# working.net
KiCad netlist of a schematic drawn in EAGLE
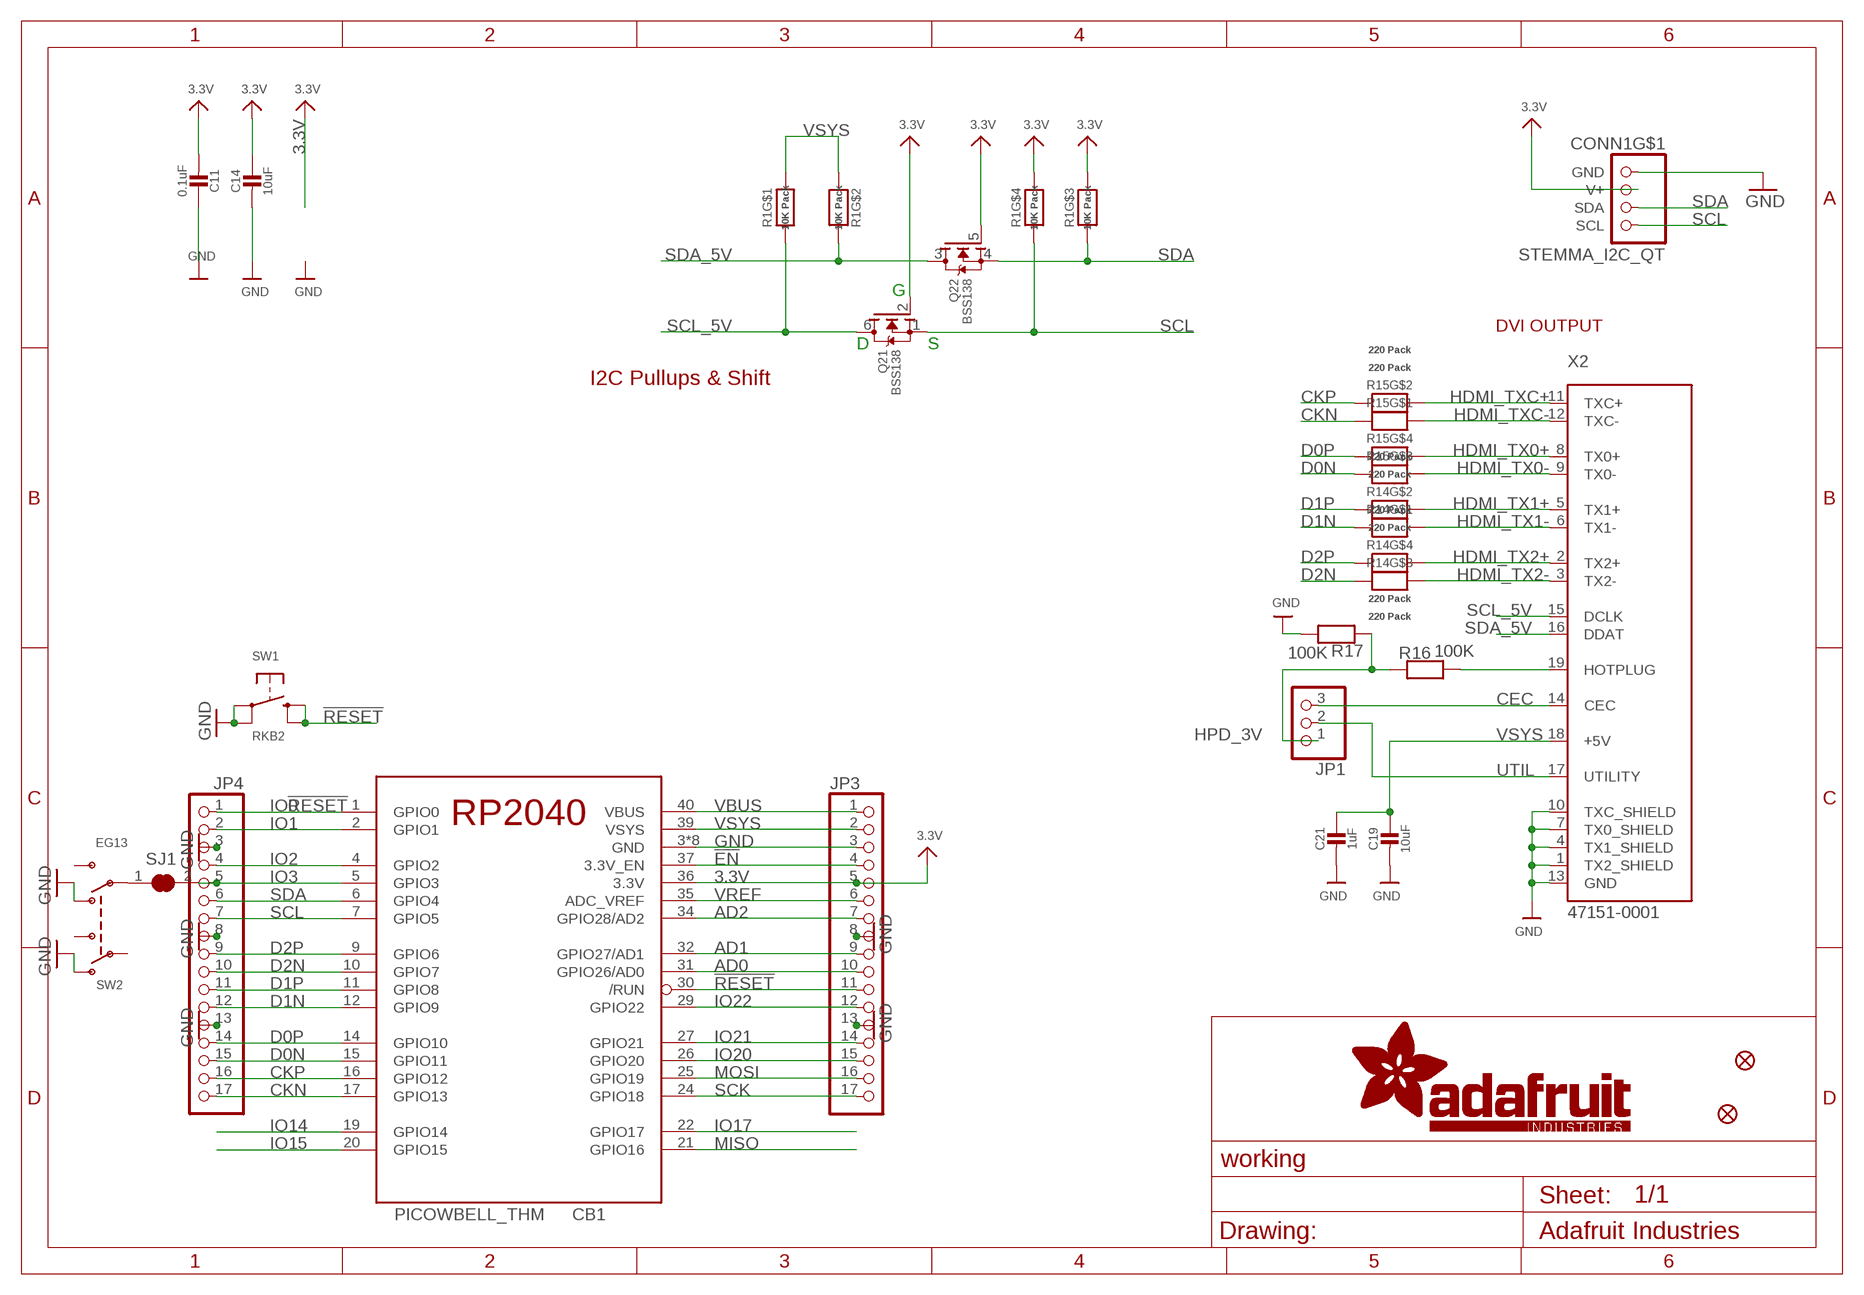
[diagram p0: schematic, sheet 1]

(export (version "E")
  (design (tool "Eeschema 10.0.6"))
  (components
    (comp (ref "C11")
      (value "0.1uF")
      (footprint "eagle-import:0603-NO")
      (libsource (lib "eagle-import") (part "CAP_CERAMIC0603_NO"))
    )
    (comp (ref "C14")
      (value "10uF")
      (footprint "eagle-import:0805-NO")
      (libsource (lib "eagle-import") (part "CAP_CERAMIC0805-NOOUTLINE"))
    )
    (comp (ref "C19")
      (value "10uF")
      (footprint "eagle-import:0805-NO")
      (fields (field (name "REV") "A"))
      (libsource (lib "eagle-import") (part "CAP_CERAMIC0805-NOOUTLINE"))
    )
    (comp (ref "C21")
      (value "1uF")
      (footprint "eagle-import:0603-NO")
      (libsource (lib "eagle-import") (part "CAP_CERAMIC0603_NO"))
    )
    (comp (ref "CB1")
      (value "PICOWBELL_THM")
      (footprint "eagle-import:PICOWBELL_THM")
      (libsource (lib "eagle-import") (part "PICOWBELL_THM"))
    )
    (comp (ref "CONN1")
      (value "STEMMA_I2C_QT")
      (footprint "eagle-import:JST_SH4")
      (libsource (lib "eagle-import") (part "STEMMA_I2C_QT"))
    )
    (comp (ref "FID1")
      (value "FIDUCIAL_1MM")
      (footprint "eagle-import:FIDUCIAL_1MM")
      (libsource (lib "eagle-import") (part "FIDUCIAL_1MM"))
    )
    (comp (ref "FID2")
      (value "FIDUCIAL_1MM")
      (footprint "eagle-import:FIDUCIAL_1MM")
      (libsource (lib "eagle-import") (part "FIDUCIAL_1MM"))
    )
    (comp (ref "JP1")
      (value "HEADER-1X3ROUND")
      (footprint "eagle-import:1X03_ROUND")
      (libsource (lib "eagle-import") (part "HEADER-1X3ROUND"))
    )
    (comp (ref "JP3")
      (value "HEADER-1X17")
      (footprint "eagle-import:1X17_ROUND70")
      (libsource (lib "eagle-import") (part "HEADER-1X17"))
    )
    (comp (ref "JP4")
      (value "HEADER-1X17")
      (footprint "eagle-import:1X17_ROUND70")
      (libsource (lib "eagle-import") (part "HEADER-1X17"))
    )
    (comp (ref "Q2")
      (value "BSS138")
      (footprint "eagle-import:SOT363")
      (libsource (lib "eagle-import") (part "MOSFET-N_DUAL"))
    )
    (comp (ref "R1")
      (value "10K Pack")
      (footprint "eagle-import:RESPACK_4X0603")
      (libsource (lib "eagle-import") (part "RESISTOR_4PACK"))
    )
    (comp (ref "R14")
      (value "220 Pack")
      (footprint "eagle-import:RESPACK_4X0603")
      (libsource (lib "eagle-import") (part "RESISTOR_4PACK"))
    )
    (comp (ref "R15")
      (value "220 Pack")
      (footprint "eagle-import:RESPACK_4X0603")
      (libsource (lib "eagle-import") (part "RESISTOR_4PACK"))
    )
    (comp (ref "R16")
      (value "100K")
      (footprint "eagle-import:0603-NO")
      (libsource (lib "eagle-import") (part "RESISTOR_0603_NOOUT"))
    )
    (comp (ref "R17")
      (value "100K")
      (footprint "eagle-import:0603-NO")
      (libsource (lib "eagle-import") (part "RESISTOR_0603_NOOUT"))
    )
    (comp (ref "SJ1")
      (value "SOLDERJUMPER_CLOSED")
      (footprint "eagle-import:SOLDERJUMPER_CLOSEDWIRE")
      (libsource (lib "eagle-import") (part "SOLDERJUMPER_CLOSED"))
    )
    (comp (ref "SW1")
      (value "RKB2")
      (footprint "eagle-import:BTN_RKB2_4.6X2.8")
      (libsource (lib "eagle-import") (part "SWITCH_TACT_SMT_RKB2"))
    )
    (comp (ref "SW2")
      (value "EG13")
      (footprint "eagle-import:EG1390")
      (libsource (lib "eagle-import") (part "SWITCH_DPDTEG1390"))
    )
    (comp (ref "X2")
      (value "47151-0001")
      (footprint "eagle-import:MINIHDMI_CNCTECH")
      (libsource (lib "eagle-import") (part "HDMI_MOLEX_47151_MINI"))
    )
  )
  (nets
    (net (code "1") (name "/AD0") (class "Default")
      (node (ref "CB1") (pin "31") (pinfunction "GPIO26/AD0_31") (pintype "bidirectional"))
      (node (ref "JP3") (pin "10") (pinfunction "10_10") (pintype "passive"))
    )
    (net (code "2") (name "/AD1") (class "Default")
      (node (ref "CB1") (pin "32") (pinfunction "GPIO27/AD1_32") (pintype "bidirectional"))
      (node (ref "JP3") (pin "9") (pinfunction "9_9") (pintype "passive"))
    )
    (net (code "3") (name "/AD2") (class "Default")
      (node (ref "CB1") (pin "34") (pinfunction "GPIO28/AD2_34") (pintype "bidirectional"))
      (node (ref "JP3") (pin "7") (pinfunction "7_7") (pintype "passive"))
    )
    (net (code "4") (name "/CEC") (class "Default")
      (node (ref "JP1") (pin "3") (pinfunction "3_3") (pintype "passive"))
      (node (ref "X2") (pin "14") (pinfunction "CEC_14") (pintype "bidirectional"))
    )
    (net (code "5") (name "/CKN") (class "Default")
      (node (ref "CB1") (pin "17") (pinfunction "GPIO13_17") (pintype "bidirectional"))
      (node (ref "JP4") (pin "17") (pinfunction "17_17") (pintype "passive"))
      (node (ref "R15") (pin "8") (pinfunction "2_8") (pintype "passive"))
    )
    (net (code "6") (name "/CKP") (class "Default")
      (node (ref "CB1") (pin "16") (pinfunction "GPIO12_16") (pintype "bidirectional"))
      (node (ref "JP4") (pin "16") (pinfunction "16_16") (pintype "passive"))
      (node (ref "R15") (pin "7") (pinfunction "2_7") (pintype "passive"))
    )
    (net (code "7") (name "/D0N") (class "Default")
      (node (ref "CB1") (pin "15") (pinfunction "GPIO11_15") (pintype "bidirectional"))
      (node (ref "JP4") (pin "15") (pinfunction "15_15") (pintype "passive"))
      (node (ref "R15") (pin "6") (pinfunction "2_6") (pintype "passive"))
    )
    (net (code "8") (name "/D0P") (class "Default")
      (node (ref "CB1") (pin "14") (pinfunction "GPIO10_14") (pintype "bidirectional"))
      (node (ref "JP4") (pin "14") (pinfunction "14_14") (pintype "passive"))
      (node (ref "R15") (pin "5") (pinfunction "2_5") (pintype "passive"))
    )
    (net (code "9") (name "/D1N") (class "Default")
      (node (ref "CB1") (pin "12") (pinfunction "GPIO9_12") (pintype "bidirectional"))
      (node (ref "JP4") (pin "12") (pinfunction "12_12") (pintype "passive"))
      (node (ref "R14") (pin "8") (pinfunction "2_8") (pintype "passive"))
    )
    (net (code "10") (name "/D1P") (class "Default")
      (node (ref "CB1") (pin "11") (pinfunction "GPIO8_11") (pintype "bidirectional"))
      (node (ref "JP4") (pin "11") (pinfunction "11_11") (pintype "passive"))
      (node (ref "R14") (pin "7") (pinfunction "2_7") (pintype "passive"))
    )
    (net (code "11") (name "/D2N") (class "Default")
      (node (ref "CB1") (pin "10") (pinfunction "GPIO7_10") (pintype "bidirectional"))
      (node (ref "JP4") (pin "10") (pinfunction "10_10") (pintype "passive"))
      (node (ref "R14") (pin "6") (pinfunction "2_6") (pintype "passive"))
    )
    (net (code "12") (name "/D2P") (class "Default")
      (node (ref "CB1") (pin "9") (pinfunction "GPIO6_9") (pintype "bidirectional"))
      (node (ref "JP4") (pin "9") (pinfunction "9_9") (pintype "passive"))
      (node (ref "R14") (pin "5") (pinfunction "2_5") (pintype "passive"))
    )
    (net (code "13") (name "/HDMI_TX0+") (class "Default")
      (node (ref "R15") (pin "4") (pinfunction "1_4") (pintype "passive"))
      (node (ref "X2") (pin "8") (pinfunction "TX0+_8") (pintype "bidirectional"))
    )
    (net (code "14") (name "/HDMI_TX0-") (class "Default")
      (node (ref "R15") (pin "3") (pinfunction "1_3") (pintype "passive"))
      (node (ref "X2") (pin "9") (pinfunction "TX0-_9") (pintype "bidirectional"))
    )
    (net (code "15") (name "/HDMI_TX1+") (class "Default")
      (node (ref "R14") (pin "2") (pinfunction "1_2") (pintype "passive"))
      (node (ref "X2") (pin "5") (pinfunction "TX1+_5") (pintype "bidirectional"))
    )
    (net (code "16") (name "/HDMI_TX1-") (class "Default")
      (node (ref "R14") (pin "1") (pinfunction "1_1") (pintype "passive"))
      (node (ref "X2") (pin "6") (pinfunction "TX1-_6") (pintype "bidirectional"))
    )
    (net (code "17") (name "/HDMI_TX2+") (class "Default")
      (node (ref "R14") (pin "4") (pinfunction "1_4") (pintype "passive"))
      (node (ref "X2") (pin "2") (pinfunction "TX2+_2") (pintype "bidirectional"))
    )
    (net (code "18") (name "/HDMI_TX2-") (class "Default")
      (node (ref "R14") (pin "3") (pinfunction "1_3") (pintype "passive"))
      (node (ref "X2") (pin "3") (pinfunction "TX2-_3") (pintype "bidirectional"))
    )
    (net (code "19") (name "/HDMI_TXC+") (class "Default")
      (node (ref "R15") (pin "2") (pinfunction "1_2") (pintype "passive"))
      (node (ref "X2") (pin "11") (pinfunction "TXC+_11") (pintype "bidirectional"))
    )
    (net (code "20") (name "/HDMI_TXC-") (class "Default")
      (node (ref "R15") (pin "1") (pinfunction "1_1") (pintype "passive"))
      (node (ref "X2") (pin "12") (pinfunction "TXC-_12") (pintype "bidirectional"))
    )
    (net (code "21") (name "/HPD_3V") (class "Default")
      (node (ref "JP1") (pin "1") (pinfunction "1_1") (pintype "passive"))
      (node (ref "R16") (pin "1") (pinfunction "1_1") (pintype "passive"))
      (node (ref "R17") (pin "1") (pinfunction "1_1") (pintype "passive"))
    )
    (net (code "22") (name "/IO0") (class "Default")
      (node (ref "CB1") (pin "1") (pinfunction "GPIO0_1") (pintype "bidirectional"))
      (node (ref "JP4") (pin "1") (pinfunction "1_1") (pintype "passive"))
    )
    (net (code "23") (name "/IO1") (class "Default")
      (node (ref "CB1") (pin "2") (pinfunction "GPIO1_2") (pintype "bidirectional"))
      (node (ref "JP4") (pin "2") (pinfunction "2_2") (pintype "passive"))
    )
    (net (code "24") (name "/IO2") (class "Default")
      (node (ref "CB1") (pin "4") (pinfunction "GPIO2_4") (pintype "bidirectional"))
      (node (ref "JP4") (pin "4") (pinfunction "4_4") (pintype "passive"))
    )
    (net (code "25") (name "/IO3") (class "Default")
      (node (ref "CB1") (pin "5") (pinfunction "GPIO3_5") (pintype "bidirectional"))
      (node (ref "JP4") (pin "5") (pinfunction "5_5") (pintype "passive"))
      (node (ref "SJ1") (pin "2") (pinfunction "2_2") (pintype "passive"))
    )
    (net (code "26") (name "/IO14") (class "Default")
      (node (ref "CB1") (pin "19") (pinfunction "GPIO14_19") (pintype "bidirectional"))
    )
    (net (code "27") (name "/IO15") (class "Default")
      (node (ref "CB1") (pin "20") (pinfunction "GPIO15_20") (pintype "bidirectional"))
    )
    (net (code "28") (name "/IO17") (class "Default")
      (node (ref "CB1") (pin "22") (pinfunction "GPIO17_22") (pintype "bidirectional"))
    )
    (net (code "29") (name "/IO20") (class "Default")
      (node (ref "CB1") (pin "26") (pinfunction "GPIO20_26") (pintype "bidirectional"))
      (node (ref "JP3") (pin "15") (pinfunction "15_15") (pintype "passive"))
    )
    (net (code "30") (name "/IO21") (class "Default")
      (node (ref "CB1") (pin "27") (pinfunction "GPIO21_27") (pintype "bidirectional"))
      (node (ref "JP3") (pin "14") (pinfunction "14_14") (pintype "passive"))
    )
    (net (code "31") (name "/IO22") (class "Default")
      (node (ref "CB1") (pin "29") (pinfunction "GPIO22_29") (pintype "bidirectional"))
      (node (ref "JP3") (pin "12") (pinfunction "12_12") (pintype "passive"))
    )
    (net (code "32") (name "/MISO") (class "Default")
      (node (ref "CB1") (pin "21") (pinfunction "GPIO16_21") (pintype "bidirectional"))
    )
    (net (code "33") (name "/MOSI") (class "Default")
      (node (ref "CB1") (pin "25") (pinfunction "GPIO19_25") (pintype "bidirectional"))
      (node (ref "JP3") (pin "16") (pinfunction "16_16") (pintype "passive"))
    )
    (net (code "34") (name "/SCK") (class "Default")
      (node (ref "CB1") (pin "24") (pinfunction "GPIO18_24") (pintype "bidirectional"))
      (node (ref "JP3") (pin "17") (pinfunction "17_17") (pintype "passive"))
    )
    (net (code "35") (name "/SCL") (class "Default")
      (node (ref "CB1") (pin "7") (pinfunction "GPIO5_7") (pintype "bidirectional"))
      (node (ref "CONN1") (pin "4") (pinfunction "SCL_4") (pintype "passive"))
      (node (ref "JP4") (pin "7") (pinfunction "7_7") (pintype "passive"))
      (node (ref "Q2") (pin "1") (pinfunction "S_1") (pintype "bidirectional"))
      (node (ref "R1") (pin "4") (pinfunction "1_4") (pintype "passive"))
    )
    (net (code "36") (name "/SCL_5V") (class "Default")
      (node (ref "Q2") (pin "6") (pinfunction "D_6") (pintype "bidirectional"))
      (node (ref "R1") (pin "8") (pinfunction "2_8") (pintype "passive"))
      (node (ref "X2") (pin "15") (pinfunction "DCLK_15") (pintype "bidirectional"))
    )
    (net (code "37") (name "/SDA") (class "Default")
      (node (ref "CB1") (pin "6") (pinfunction "GPIO4_6") (pintype "bidirectional"))
      (node (ref "CONN1") (pin "3") (pinfunction "SDA_3") (pintype "passive"))
      (node (ref "JP4") (pin "6") (pinfunction "6_6") (pintype "passive"))
      (node (ref "Q2") (pin "4") (pinfunction "S_4") (pintype "bidirectional"))
      (node (ref "R1") (pin "3") (pinfunction "1_3") (pintype "passive"))
    )
    (net (code "38") (name "/SDA_5V") (class "Default")
      (node (ref "Q2") (pin "3") (pinfunction "D_3") (pintype "bidirectional"))
      (node (ref "R1") (pin "7") (pinfunction "2_7") (pintype "passive"))
      (node (ref "X2") (pin "16") (pinfunction "DDAT_16") (pintype "bidirectional"))
    )
    (net (code "39") (name "/UTIL") (class "Default")
      (node (ref "JP1") (pin "2") (pinfunction "2_2") (pintype "passive"))
      (node (ref "X2") (pin "17") (pinfunction "UTILITY_17") (pintype "bidirectional"))
    )
    (net (code "40") (name "/VBUS") (class "Default")
      (node (ref "CB1") (pin "40") (pinfunction "VBUS_40") (pintype "power_in"))
      (node (ref "JP3") (pin "1") (pinfunction "1_1") (pintype "passive"))
    )
    (net (code "41") (name "/VREF") (class "Default")
      (node (ref "CB1") (pin "35") (pinfunction "ADC_VREF_35") (pintype "passive"))
      (node (ref "JP3") (pin "6") (pinfunction "6_6") (pintype "passive"))
    )
    (net (code "42") (name "/VSYS") (class "Default")
      (node (ref "C19") (pin "1") (pinfunction "1_1") (pintype "passive"))
      (node (ref "C21") (pin "1") (pinfunction "1_1") (pintype "passive"))
      (node (ref "CB1") (pin "39") (pinfunction "VSYS_39") (pintype "power_in"))
      (node (ref "JP3") (pin "2") (pinfunction "2_2") (pintype "passive"))
      (node (ref "R1") (pin "1") (pinfunction "1_1") (pintype "passive"))
      (node (ref "R1") (pin "2") (pinfunction "1_2") (pintype "passive"))
      (node (ref "X2") (pin "18") (pinfunction "+5V_18") (pintype "power_in"))
    )
    (net (code "43") (name "/~{EN}") (class "Default")
      (node (ref "CB1") (pin "37") (pinfunction "3.3V_EN_37") (pintype "passive"))
      (node (ref "JP3") (pin "4") (pinfunction "4_4") (pintype "passive"))
    )
    (net (code "44") (name "/~{RESET}") (class "Default")
      (node (ref "CB1") (pin "30") (pinfunction "/RUN_30") (pintype "bidirectional"))
      (node (ref "JP3") (pin "11") (pinfunction "11_11") (pintype "passive"))
      (node (ref "SW1") (pin "B") (pinfunction "S_B") (pintype "passive"))
      (node (ref "SW1") (pin "B'") (pinfunction "S1_B'") (pintype "passive"))
    )
    (net (code "45") (name "3.3V") (class "Default")
      (node (ref "C11") (pin "2") (pinfunction "2_2") (pintype "passive"))
      (node (ref "C14") (pin "1") (pinfunction "1_1") (pintype "passive"))
      (node (ref "CB1") (pin "36") (pinfunction "3.3V_36") (pintype "power_in"))
      (node (ref "CONN1") (pin "2") (pinfunction "V+_2") (pintype "passive"))
      (node (ref "JP3") (pin "5") (pinfunction "5_5") (pintype "passive"))
      (node (ref "Q2") (pin "2") (pinfunction "G_2") (pintype "bidirectional"))
      (node (ref "Q2") (pin "5") (pinfunction "G_5") (pintype "bidirectional"))
      (node (ref "R1") (pin "5") (pinfunction "2_5") (pintype "passive"))
      (node (ref "R1") (pin "6") (pinfunction "2_6") (pintype "passive"))
    )
    (net (code "46") (name "GND") (class "Default")
      (node (ref "C11") (pin "1") (pinfunction "1_1") (pintype "passive"))
      (node (ref "C14") (pin "2") (pinfunction "2_2") (pintype "passive"))
      (node (ref "C19") (pin "2") (pinfunction "2_2") (pintype "passive"))
      (node (ref "C21") (pin "2") (pinfunction "2_2") (pintype "passive"))
      (node (ref "CB1") (pin "13") (pinfunction "GND_13") (pintype "power_in"))
      (node (ref "CB1") (pin "18") (pinfunction "GND_18") (pintype "power_in"))
      (node (ref "CB1") (pin "23") (pinfunction "GND_23") (pintype "power_in"))
      (node (ref "CB1") (pin "28") (pinfunction "GND_28") (pintype "power_in"))
      (node (ref "CB1") (pin "3") (pinfunction "GND_3") (pintype "power_in"))
      (node (ref "CB1") (pin "33") (pinfunction "GND_33") (pintype "power_in"))
      (node (ref "CB1") (pin "38") (pinfunction "GND_38") (pintype "power_in"))
      (node (ref "CB1") (pin "8") (pinfunction "GND_8") (pintype "power_in"))
      (node (ref "CONN1") (pin "1") (pinfunction "GND_1") (pintype "passive"))
      (node (ref "JP3") (pin "13") (pinfunction "13_13") (pintype "passive"))
      (node (ref "JP3") (pin "3") (pinfunction "3_3") (pintype "passive"))
      (node (ref "JP3") (pin "8") (pinfunction "8_8") (pintype "passive"))
      (node (ref "JP4") (pin "13") (pinfunction "13_13") (pintype "passive"))
      (node (ref "JP4") (pin "3") (pinfunction "3_3") (pintype "passive"))
      (node (ref "JP4") (pin "8") (pinfunction "8_8") (pintype "passive"))
      (node (ref "R17") (pin "2") (pinfunction "2_2") (pintype "passive"))
      (node (ref "SW1") (pin "A") (pinfunction "P_A") (pintype "passive"))
      (node (ref "SW1") (pin "A'") (pinfunction "P1_A'") (pintype "passive"))
      (node (ref "SW2") (pin "O1") (pinfunction "O1_O1") (pintype "passive"))
      (node (ref "SW2") (pin "O2") (pinfunction "O2_O2") (pintype "passive"))
      (node (ref "X2") (pin "1") (pinfunction "TX2_SHIELD_1") (pintype "power_in"))
      (node (ref "X2") (pin "10") (pinfunction "TXC_SHIELD_10") (pintype "power_in"))
      (node (ref "X2") (pin "13") (pinfunction "GND_13") (pintype "power_in"))
      (node (ref "X2") (pin "4") (pinfunction "TX1_SHIELD_4") (pintype "power_in"))
      (node (ref "X2") (pin "7") (pinfunction "TX0_SHIELD_7") (pintype "power_in"))
    )
    (net (code "47") (name "Net-(SJ1-Pad1)") (class "Default")
      (node (ref "SJ1") (pin "1") (pinfunction "1_1") (pintype "passive"))
      (node (ref "SW2") (pin "P2") (pinfunction "P2_P2") (pintype "passive"))
    )
    (net (code "48") (name "Net-(X2A-HOTPLUG)") (class "Default")
      (node (ref "R16") (pin "2") (pinfunction "2_2") (pintype "passive"))
      (node (ref "X2") (pin "19") (pinfunction "HOTPLUG_19") (pintype "bidirectional"))
    )
    (net (code "49") (name "unconnected-(SW2-PadP1)") (class "Default")
      (node (ref "SW2") (pin "P1") (pinfunction "P1_P1") (pintype "passive"))
    )
    (net (code "50") (name "unconnected-(SW2-PadS1)") (class "Default")
      (node (ref "SW2") (pin "S1") (pinfunction "S1_S1") (pintype "passive"))
    )
    (net (code "51") (name "unconnected-(SW2-PadS2)") (class "Default")
      (node (ref "SW2") (pin "S2") (pinfunction "S2_S2") (pintype "passive"))
    )
  )
)
